# DAPlink-LPC11U35-v1_1_0.net
KiCad netlist of a schematic drawn in EAGLE
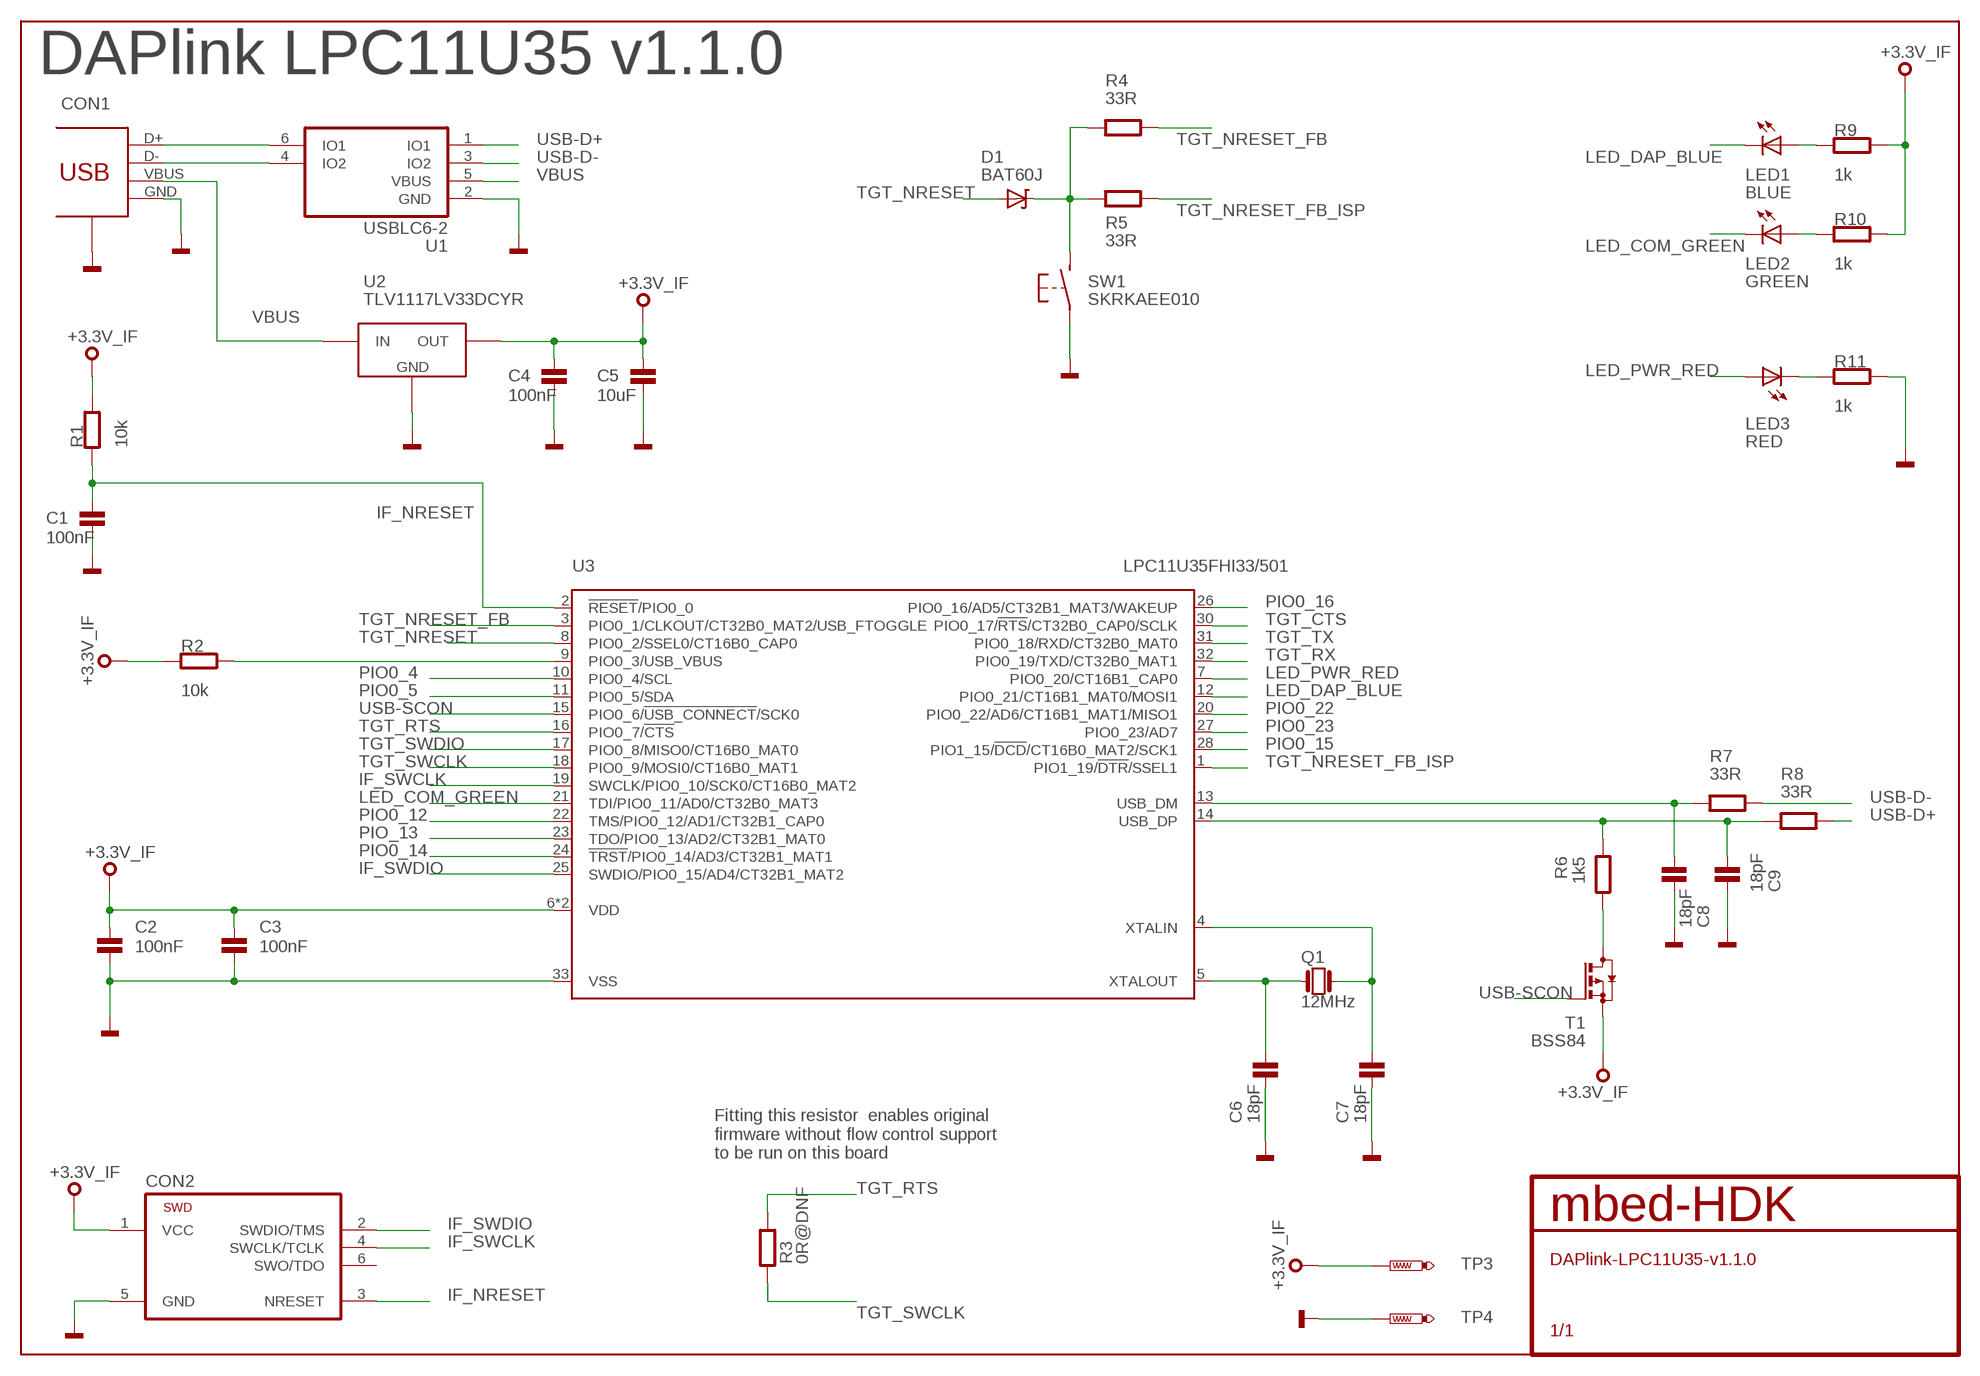
[diagram p0: schematic, sheet 1]

(export (version "E")
  (design (tool "Eeschema 10.0.6"))
  (components
    (comp (ref "C1")
      (value "100nF")
      (footprint "eagle-import:0603")
      (libsource (lib "eagle-import") (part "C0603"))
    )
    (comp (ref "C2")
      (value "100nF")
      (footprint "eagle-import:0603")
      (libsource (lib "eagle-import") (part "C0603"))
    )
    (comp (ref "C3")
      (value "100nF")
      (footprint "eagle-import:0603")
      (libsource (lib "eagle-import") (part "C0603"))
    )
    (comp (ref "C4")
      (value "100nF")
      (footprint "eagle-import:0603")
      (libsource (lib "eagle-import") (part "C0603"))
    )
    (comp (ref "C5")
      (value "10uF")
      (footprint "eagle-import:0603")
      (libsource (lib "eagle-import") (part "C0603"))
    )
    (comp (ref "C6")
      (value "18pF")
      (footprint "eagle-import:0603")
      (libsource (lib "eagle-import") (part "C0603"))
    )
    (comp (ref "C7")
      (value "18pF")
      (footprint "eagle-import:0603")
      (libsource (lib "eagle-import") (part "C0603"))
    )
    (comp (ref "C8")
      (value "18pF")
      (footprint "eagle-import:0603")
      (libsource (lib "eagle-import") (part "C0603"))
    )
    (comp (ref "C9")
      (value "18pF")
      (footprint "eagle-import:0603")
      (libsource (lib "eagle-import") (part "C0603"))
    )
    (comp (ref "CON1")
      (value "47346-0001")
      (footprint "eagle-import:USB-MICRO-B-H")
      (fields (field (name "MF") "MOLEX"))
      (libsource (lib "eagle-import") (part "47346-0001"))
    )
    (comp (ref "CON2")
      (value "TC2030-CTX-NL")
      (footprint "eagle-import:TC2030-CTX-NL")
      (libsource (lib "eagle-import") (part "TC2030-CTX-NL"))
    )
    (comp (ref "D1")
      (value "BAT60J")
      (footprint "eagle-import:SOD323")
      (fields (field (name "MF") "STMicroelectronics"))
      (libsource (lib "eagle-import") (part "BAT60J"))
    )
    (comp (ref "LED1")
      (value "BLUE")
      (footprint "eagle-import:CHIPLED_0603")
      (libsource (lib "eagle-import") (part "LED0603"))
    )
    (comp (ref "LED2")
      (value "GREEN")
      (footprint "eagle-import:CHIPLED_0603")
      (libsource (lib "eagle-import") (part "LED0603"))
    )
    (comp (ref "LED3")
      (value "RED")
      (footprint "eagle-import:CHIPLED_0603")
      (libsource (lib "eagle-import") (part "LED0603"))
    )
    (comp (ref "Q1")
      (value "12MHz")
      (footprint "eagle-import:3.2X.2.5")
      (libsource (lib "eagle-import") (part "Q_3.2X2.5"))
    )
    (comp (ref "R1")
      (value "10k")
      (footprint "eagle-import:0603")
      (libsource (lib "eagle-import") (part "R0603"))
    )
    (comp (ref "R2")
      (value "10k")
      (footprint "eagle-import:0603")
      (libsource (lib "eagle-import") (part "R0603"))
    )
    (comp (ref "R3")
      (value "0R@DNF")
      (footprint "eagle-import:0603")
      (libsource (lib "eagle-import") (part "R0603"))
    )
    (comp (ref "R4")
      (value "33R")
      (footprint "eagle-import:0603")
      (libsource (lib "eagle-import") (part "R0603"))
    )
    (comp (ref "R5")
      (value "33R")
      (footprint "eagle-import:0603")
      (libsource (lib "eagle-import") (part "R0603"))
    )
    (comp (ref "R6")
      (value "1k5")
      (footprint "eagle-import:0603")
      (libsource (lib "eagle-import") (part "R0603"))
    )
    (comp (ref "R7")
      (value "33R")
      (footprint "eagle-import:0603")
      (libsource (lib "eagle-import") (part "R0603"))
    )
    (comp (ref "R8")
      (value "33R")
      (footprint "eagle-import:0603")
      (libsource (lib "eagle-import") (part "R0603"))
    )
    (comp (ref "R9")
      (value "1k")
      (footprint "eagle-import:0603")
      (libsource (lib "eagle-import") (part "R0603"))
    )
    (comp (ref "R10")
      (value "1k")
      (footprint "eagle-import:0603")
      (libsource (lib "eagle-import") (part "R0603"))
    )
    (comp (ref "R11")
      (value "1k")
      (footprint "eagle-import:0603")
      (libsource (lib "eagle-import") (part "R0603"))
    )
    (comp (ref "SW1")
      (value "SKRKAEE010")
      (footprint "eagle-import:SKRKAEE010")
      (fields (field (name "MF") "ALPS"))
      (libsource (lib "eagle-import") (part "SKRKAEE010"))
    )
    (comp (ref "T1")
      (value "BSS84")
      (footprint "eagle-import:SOT23-3")
      (fields (field (name "MF") "Fairchild Semiconductor"))
      (libsource (lib "eagle-import") (part "BSS84"))
    )
    (comp (ref "TP3")
      (value "PTR1TP07R")
      (footprint "eagle-import:TP07R")
      (libsource (lib "eagle-import") (part "PTR1TP07R"))
    )
    (comp (ref "TP4")
      (value "PTR1TP07R")
      (footprint "eagle-import:TP07R")
      (libsource (lib "eagle-import") (part "PTR1TP07R"))
    )
    (comp (ref "U1")
      (value "USBLC6-2SC6")
      (footprint "eagle-import:SOT23-6L")
      (libsource (lib "eagle-import") (part "USBLC6-2SC6"))
    )
    (comp (ref "U2")
      (value "TLV1117LV33DCYR")
      (footprint "eagle-import:SOT223")
      (fields (field (name "MF") "Texas Instruments"))
      (libsource (lib "eagle-import") (part "TLV1117LV33DCYR"))
    )
    (comp (ref "U3")
      (value "LPC11U35FHI33/501")
      (footprint "eagle-import:SOT617-3")
      (fields (field (name "MF") "NXP"))
      (libsource (lib "eagle-import") (part "LPC11U35FHI33/501"))
    )
  )
  (nets
    (net (code "1") (name "+3.3V_IF") (class "Default")
      (node (ref "C2") (pin "1") (pinfunction "P$1_1") (pintype "passive"))
      (node (ref "C3") (pin "1") (pinfunction "P$1_1") (pintype "passive"))
      (node (ref "C4") (pin "1") (pinfunction "P$1_1") (pintype "passive"))
      (node (ref "C5") (pin "1") (pinfunction "P$1_1") (pintype "passive"))
      (node (ref "CON2") (pin "1") (pinfunction "VCC_1") (pintype "passive"))
      (node (ref "R1") (pin "2") (pinfunction "P$2_2") (pintype "passive"))
      (node (ref "R10") (pin "2") (pinfunction "P$2_2") (pintype "passive"))
      (node (ref "R2") (pin "1") (pinfunction "P$1_1") (pintype "passive"))
      (node (ref "R9") (pin "2") (pinfunction "P$2_2") (pintype "passive"))
      (node (ref "T1") (pin "2") (pinfunction "S_2") (pintype "passive"))
      (node (ref "TP3") (pin "TP") (pinfunction "TP_TP") (pintype "input"))
      (node (ref "U2") (pin "2") (pinfunction "OUT_2") (pintype "bidirectional"))
      (node (ref "U2") (pin "4") (pinfunction "OUT_4") (pintype "bidirectional"))
      (node (ref "U3") (pin "29") (pinfunction "VDD_29") (pintype "passive"))
      (node (ref "U3") (pin "6") (pinfunction "VDD_6") (pintype "passive"))
    )
    (net (code "2") (name "/IF_NRESET") (class "Default")
      (node (ref "C1") (pin "1") (pinfunction "P$1_1") (pintype "passive"))
      (node (ref "CON2") (pin "3") (pinfunction "NRESET_3") (pintype "passive"))
      (node (ref "R1") (pin "1") (pinfunction "P$1_1") (pintype "passive"))
      (node (ref "U3") (pin "2") (pinfunction "~{RESET}/PIO0_0_2") (pintype "bidirectional"))
    )
    (net (code "3") (name "/IF_SWCLK") (class "Default")
      (node (ref "CON2") (pin "4") (pinfunction "SWCLK/TCLK_4") (pintype "passive"))
      (node (ref "U3") (pin "19") (pinfunction "SWCLK/PIO0_10/SCK0/CT16B0_MAT2_19") (pintype "bidirectional"))
    )
    (net (code "4") (name "/IF_SWDIO") (class "Default")
      (node (ref "CON2") (pin "2") (pinfunction "SWDIO/TMS_2") (pintype "passive"))
      (node (ref "U3") (pin "25") (pinfunction "SWDIO/PIO0_15/AD4/CT32B1_MAT2_25") (pintype "bidirectional"))
    )
    (net (code "5") (name "/LED_COM_GREEN") (class "Default")
      (node (ref "LED2") (pin "C") (pinfunction "C_C") (pintype "passive"))
      (node (ref "U3") (pin "21") (pinfunction "TDI/PIO0_11/AD0/CT32B0_MAT3_21") (pintype "bidirectional"))
    )
    (net (code "6") (name "/LED_DAP_BLUE") (class "Default")
      (node (ref "LED1") (pin "C") (pinfunction "C_C") (pintype "passive"))
      (node (ref "U3") (pin "12") (pinfunction "PIO0_21/CT16B1_MAT0/MOSI1_12") (pintype "bidirectional"))
    )
    (net (code "7") (name "/LED_PWR_RED") (class "Default")
      (node (ref "LED3") (pin "A") (pinfunction "A_A") (pintype "passive"))
      (node (ref "U3") (pin "7") (pinfunction "PIO0_20/CT16B1_CAP0_7") (pintype "bidirectional"))
    )
    (net (code "8") (name "/PIO0_4") (class "Default")
      (node (ref "U3") (pin "10") (pinfunction "PIO0_4/SCL_10") (pintype "bidirectional"))
    )
    (net (code "9") (name "/PIO0_5") (class "Default")
      (node (ref "U3") (pin "11") (pinfunction "PIO0_5/SDA_11") (pintype "bidirectional"))
    )
    (net (code "10") (name "/PIO0_12") (class "Default")
      (node (ref "U3") (pin "22") (pinfunction "TMS/PIO0_12/AD1/CT32B1_CAP0_22") (pintype "bidirectional"))
    )
    (net (code "11") (name "/PIO0_14") (class "Default")
      (node (ref "U3") (pin "24") (pinfunction "~{TRST}/PIO0_14/AD3/CT32B1_MAT1_24") (pintype "bidirectional"))
    )
    (net (code "12") (name "/PIO0_15") (class "Default")
      (node (ref "U3") (pin "28") (pinfunction "PIO1_15/~{DCD}/CT16B0_MAT2/SCK1_28") (pintype "bidirectional"))
    )
    (net (code "13") (name "/PIO0_16") (class "Default")
      (node (ref "U3") (pin "26") (pinfunction "PIO0_16/AD5/CT32B1_MAT3/WAKEUP_26") (pintype "bidirectional"))
    )
    (net (code "14") (name "/PIO0_22") (class "Default")
      (node (ref "U3") (pin "20") (pinfunction "PIO0_22/AD6/CT16B1_MAT1/MISO1_20") (pintype "bidirectional"))
    )
    (net (code "15") (name "/PIO0_23") (class "Default")
      (node (ref "U3") (pin "27") (pinfunction "PIO0_23/AD7_27") (pintype "bidirectional"))
    )
    (net (code "16") (name "/PIO_13") (class "Default")
      (node (ref "U3") (pin "23") (pinfunction "TDO/PIO0_13/AD2/CT32B1_MAT0_23") (pintype "bidirectional"))
    )
    (net (code "17") (name "/TGT_CTS") (class "Default")
      (node (ref "U3") (pin "30") (pinfunction "PIO0_17/~{RTS}/CT32B0_CAP0/SCLK_30") (pintype "bidirectional"))
    )
    (net (code "18") (name "/TGT_NRESET") (class "Default")
      (node (ref "D1") (pin "A") (pinfunction "A_A") (pintype "passive"))
      (node (ref "U3") (pin "8") (pinfunction "PIO0_2/SSEL0/CT16B0_CAP0_8") (pintype "bidirectional"))
    )
    (net (code "19") (name "/TGT_NRESET_FB") (class "Default")
      (node (ref "R4") (pin "1") (pinfunction "P$1_1") (pintype "passive"))
      (node (ref "U3") (pin "3") (pinfunction "PIO0_1/CLKOUT/CT32B0_MAT2/USB_FTOGGLE_3") (pintype "bidirectional"))
    )
    (net (code "20") (name "/TGT_NRESET_FB_ISP") (class "Default")
      (node (ref "R5") (pin "1") (pinfunction "P$1_1") (pintype "passive"))
      (node (ref "U3") (pin "1") (pinfunction "PIO1_19/~{DTR}/SSEL1_1") (pintype "bidirectional"))
    )
    (net (code "21") (name "/TGT_RTS") (class "Default")
      (node (ref "R3") (pin "2") (pinfunction "P$2_2") (pintype "passive"))
      (node (ref "U3") (pin "16") (pinfunction "PIO0_7/~{CTS}_16") (pintype "bidirectional"))
    )
    (net (code "22") (name "/TGT_RX") (class "Default")
      (node (ref "U3") (pin "32") (pinfunction "PIO0_19/TXD/CT32B0_MAT1_32") (pintype "bidirectional"))
    )
    (net (code "23") (name "/TGT_SWCLK") (class "Default")
      (node (ref "R3") (pin "1") (pinfunction "P$1_1") (pintype "passive"))
      (node (ref "U3") (pin "18") (pinfunction "PIO0_9/MOSI0/CT16B0_MAT1_18") (pintype "bidirectional"))
    )
    (net (code "24") (name "/TGT_SWDIO") (class "Default")
      (node (ref "U3") (pin "17") (pinfunction "PIO0_8/MISO0/CT16B0_MAT0_17") (pintype "bidirectional"))
    )
    (net (code "25") (name "/TGT_TX") (class "Default")
      (node (ref "U3") (pin "31") (pinfunction "PIO0_18/RXD/CT32B0_MAT0_31") (pintype "bidirectional"))
    )
    (net (code "26") (name "/USB-D+") (class "Default")
      (node (ref "R8") (pin "1") (pinfunction "P$1_1") (pintype "passive"))
      (node (ref "U1") (pin "1") (pinfunction "IO1_1") (pintype "bidirectional"))
    )
    (net (code "27") (name "/USB-D-") (class "Default")
      (node (ref "R7") (pin "1") (pinfunction "P$1_1") (pintype "passive"))
      (node (ref "U1") (pin "3") (pinfunction "IO2_3") (pintype "bidirectional"))
    )
    (net (code "28") (name "/USB-SCON") (class "Default")
      (node (ref "T1") (pin "1") (pinfunction "G_1") (pintype "passive"))
      (node (ref "U3") (pin "15") (pinfunction "PIO0_6/~{USB_CONNECT}/SCK0_15") (pintype "bidirectional"))
    )
    (net (code "29") (name "/VBUS") (class "Default")
      (node (ref "CON1") (pin "VBUS") (pinfunction "VBUS_VBUS") (pintype "bidirectional"))
      (node (ref "U1") (pin "5") (pinfunction "VBUS_5") (pintype "bidirectional"))
      (node (ref "U2") (pin "3") (pinfunction "IN_3") (pintype "bidirectional"))
    )
    (net (code "30") (name "GND") (class "Default")
      (node (ref "C1") (pin "2") (pinfunction "P$2_2") (pintype "passive"))
      (node (ref "C2") (pin "2") (pinfunction "P$2_2") (pintype "passive"))
      (node (ref "C3") (pin "2") (pinfunction "P$2_2") (pintype "passive"))
      (node (ref "C4") (pin "2") (pinfunction "P$2_2") (pintype "passive"))
      (node (ref "C5") (pin "2") (pinfunction "P$2_2") (pintype "passive"))
      (node (ref "C6") (pin "2") (pinfunction "P$2_2") (pintype "passive"))
      (node (ref "C7") (pin "2") (pinfunction "P$2_2") (pintype "passive"))
      (node (ref "C8") (pin "2") (pinfunction "P$2_2") (pintype "passive"))
      (node (ref "C9") (pin "2") (pinfunction "P$2_2") (pintype "passive"))
      (node (ref "CON1") (pin "GND") (pinfunction "GND_GND") (pintype "bidirectional"))
      (node (ref "CON1") (pin "GND1") (pinfunction "SHEILD_GND1") (pintype "bidirectional"))
      (node (ref "CON1") (pin "GND2") (pinfunction "SHEILD_GND2") (pintype "bidirectional"))
      (node (ref "CON1") (pin "GND3") (pinfunction "SHEILD_GND3") (pintype "bidirectional"))
      (node (ref "CON1") (pin "GND4") (pinfunction "SHEILD_GND4") (pintype "bidirectional"))
      (node (ref "CON2") (pin "5") (pinfunction "GND_5") (pintype "passive"))
      (node (ref "R11") (pin "2") (pinfunction "P$2_2") (pintype "passive"))
      (node (ref "SW1") (pin "P$1") (pinfunction "P_P$1") (pintype "passive"))
      (node (ref "TP4") (pin "TP") (pinfunction "TP_TP") (pintype "input"))
      (node (ref "U1") (pin "2") (pinfunction "GND_2") (pintype "bidirectional"))
      (node (ref "U2") (pin "1") (pinfunction "GND_1") (pintype "bidirectional"))
      (node (ref "U3") (pin "33") (pinfunction "VSS_33") (pintype "passive"))
    )
    (net (code "31") (name "Net-(C6-P$1)") (class "Default")
      (node (ref "C6") (pin "1") (pinfunction "P$1_1") (pintype "passive"))
      (node (ref "Q1") (pin "P$1") (pinfunction "1_P$1") (pintype "passive"))
      (node (ref "U3") (pin "5") (pinfunction "XTALOUT_5") (pintype "output"))
    )
    (net (code "32") (name "Net-(C7-P$1)") (class "Default")
      (node (ref "C7") (pin "1") (pinfunction "P$1_1") (pintype "passive"))
      (node (ref "Q1") (pin "P$3") (pinfunction "2_P$3") (pintype "passive"))
      (node (ref "U3") (pin "4") (pinfunction "XTALIN_4") (pintype "input"))
    )
    (net (code "33") (name "Net-(C8-P$1)") (class "Default")
      (node (ref "C8") (pin "1") (pinfunction "P$1_1") (pintype "passive"))
      (node (ref "R7") (pin "2") (pinfunction "P$2_2") (pintype "passive"))
      (node (ref "U3") (pin "13") (pinfunction "USB_DM_13") (pintype "bidirectional"))
    )
    (net (code "34") (name "Net-(C9-P$1)") (class "Default")
      (node (ref "C9") (pin "1") (pinfunction "P$1_1") (pintype "passive"))
      (node (ref "R6") (pin "2") (pinfunction "P$2_2") (pintype "passive"))
      (node (ref "R8") (pin "2") (pinfunction "P$2_2") (pintype "passive"))
      (node (ref "U3") (pin "14") (pinfunction "USB_DP_14") (pintype "bidirectional"))
    )
    (net (code "35") (name "Net-(CON1-PadD+)") (class "Default")
      (node (ref "CON1") (pin "D+") (pinfunction "D+_D+") (pintype "bidirectional"))
      (node (ref "U1") (pin "6") (pinfunction "IO1_6") (pintype "bidirectional"))
    )
    (net (code "36") (name "Net-(CON1-PadD-)") (class "Default")
      (node (ref "CON1") (pin "D-") (pinfunction "D-_D-") (pintype "bidirectional"))
      (node (ref "U1") (pin "4") (pinfunction "IO2_4") (pintype "bidirectional"))
    )
    (net (code "37") (name "Net-(R2-P$2)") (class "Default")
      (node (ref "R2") (pin "2") (pinfunction "P$2_2") (pintype "passive"))
      (node (ref "U3") (pin "9") (pinfunction "PIO0_3/USB_VBUS_9") (pintype "bidirectional"))
    )
    (net (code "38") (name "Net-(R4-P$2)") (class "Default")
      (node (ref "D1") (pin "K") (pinfunction "K_K") (pintype "passive"))
      (node (ref "R4") (pin "2") (pinfunction "P$2_2") (pintype "passive"))
      (node (ref "R5") (pin "2") (pinfunction "P$2_2") (pintype "passive"))
      (node (ref "SW1") (pin "P$2") (pinfunction "S_P$2") (pintype "passive"))
    )
    (net (code "39") (name "Net-(R6-P$1)") (class "Default")
      (node (ref "R6") (pin "1") (pinfunction "P$1_1") (pintype "passive"))
      (node (ref "T1") (pin "3") (pinfunction "D_3") (pintype "passive"))
    )
    (net (code "40") (name "Net-(R9-P$1)") (class "Default")
      (node (ref "LED1") (pin "A") (pinfunction "A_A") (pintype "passive"))
      (node (ref "R9") (pin "1") (pinfunction "P$1_1") (pintype "passive"))
    )
    (net (code "41") (name "Net-(R10-P$1)") (class "Default")
      (node (ref "LED2") (pin "A") (pinfunction "A_A") (pintype "passive"))
      (node (ref "R10") (pin "1") (pinfunction "P$1_1") (pintype "passive"))
    )
    (net (code "42") (name "Net-(R11-P$1)") (class "Default")
      (node (ref "LED3") (pin "C") (pinfunction "C_C") (pintype "passive"))
      (node (ref "R11") (pin "1") (pinfunction "P$1_1") (pintype "passive"))
    )
    (net (code "43") (name "unconnected-(CON2-SWO{slash}TDO-Pad6)") (class "Default")
      (node (ref "CON2") (pin "6") (pinfunction "SWO/TDO_6") (pintype "passive"))
    )
  )
)
